# usblink.net
KiCad netlist of a schematic drawn in EAGLE
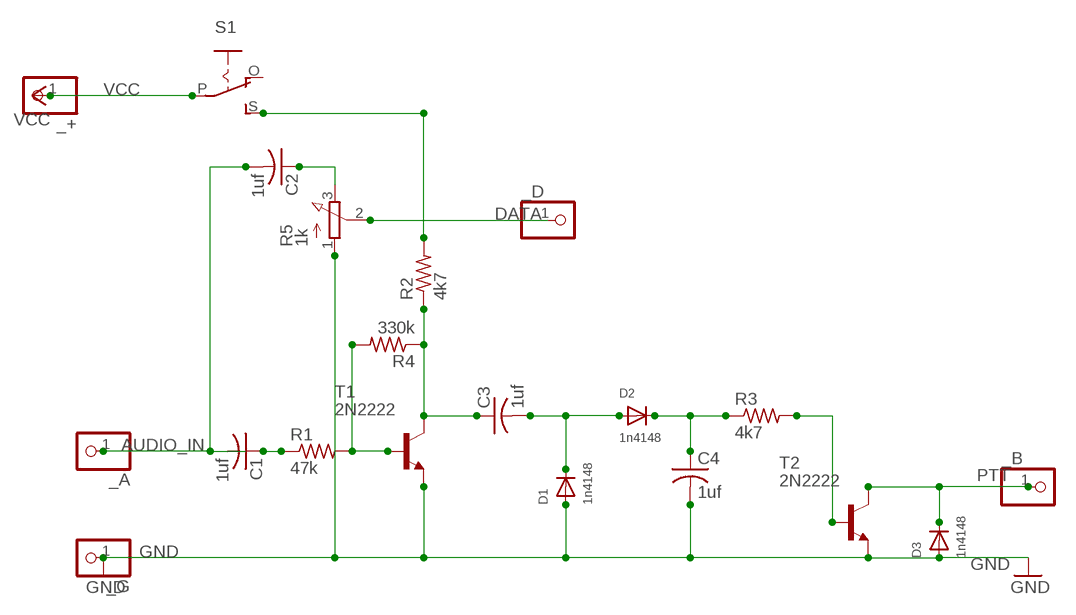
[diagram p0: schematic, sheet 1]

(export (version "E")
  (design (tool "Eeschema 10.0.6"))
  (components
    (comp (ref "C1")
      (value "1uf")
      (footprint "eagle-import:C025-030X050")
      (libsource (lib "eagle-import") (part "C-US025-030X050"))
    )
    (comp (ref "C2")
      (value "1uf")
      (footprint "eagle-import:C025-030X050")
      (libsource (lib "eagle-import") (part "C-US025-030X050"))
    )
    (comp (ref "C3")
      (value "1uf")
      (footprint "eagle-import:C025-030X050")
      (libsource (lib "eagle-import") (part "C-US025-030X050"))
    )
    (comp (ref "C4")
      (value "1uf")
      (footprint "eagle-import:C025-030X050")
      (libsource (lib "eagle-import") (part "C-US025-030X050"))
    )
    (comp (ref "D1")
      (value "1n4148")
      (footprint "eagle-import:DO-1N4148")
      (libsource (lib "eagle-import") (part "DIODEDO-1N4148"))
    )
    (comp (ref "D2")
      (value "1n4148")
      (footprint "eagle-import:DO-1N4148")
      (libsource (lib "eagle-import") (part "DIODEDO-1N4148"))
    )
    (comp (ref "D3")
      (value "1n4148")
      (footprint "eagle-import:DO-1N4148")
      (libsource (lib "eagle-import") (part "DIODEDO-1N4148"))
    )
    (comp (ref "R1")
      (value "47k")
      (footprint "eagle-import:0204_7")
      (libsource (lib "eagle-import") (part "R-US_0204/7"))
    )
    (comp (ref "R2")
      (value "4k7")
      (footprint "eagle-import:0204_7")
      (libsource (lib "eagle-import") (part "R-US_0204/7"))
    )
    (comp (ref "R3")
      (value "4k7")
      (footprint "eagle-import:0204_7")
      (libsource (lib "eagle-import") (part "R-US_0204/7"))
    )
    (comp (ref "R4")
      (value "330k")
      (footprint "eagle-import:0204_7")
      (libsource (lib "eagle-import") (part "R-US_0204/7"))
    )
    (comp (ref "R5")
      (value "1k")
      (footprint "eagle-import:3RP_1610N")
      (libsource (lib "eagle-import") (part "3RP/1610N"))
    )
    (comp (ref "S1")
      (value "EG1218S")
      (footprint "eagle-import:EG1218")
      (libsource (lib "eagle-import") (part "EG1218S"))
    )
    (comp (ref "T1")
      (value "2N2222")
      (footprint "eagle-import:TO92-EBC-OVAL")
      (libsource (lib "eagle-import") (part "2N2222"))
    )
    (comp (ref "T2")
      (value "2N2222")
      (footprint "eagle-import:TO92-EBC-OVAL")
      (libsource (lib "eagle-import") (part "2N2222"))
    )
    (comp (ref "_+")
      (value "PINHD-1X1CB")
      (footprint "eagle-import:1X01-CLEANBIG")
      (libsource (lib "eagle-import") (part "PINHD-1X1CB"))
    )
    (comp (ref "_A")
      (value "PINHD-1X1CB")
      (footprint "eagle-import:1X01-CLEANBIG")
      (libsource (lib "eagle-import") (part "PINHD-1X1CB"))
    )
    (comp (ref "_B")
      (value "PINHD-1X1CB")
      (footprint "eagle-import:1X01-CLEANBIG")
      (libsource (lib "eagle-import") (part "PINHD-1X1CB"))
    )
    (comp (ref "_D")
      (value "PINHD-1X1CB")
      (footprint "eagle-import:1X01-CLEANBIG")
      (libsource (lib "eagle-import") (part "PINHD-1X1CB"))
    )
    (comp (ref "_G")
      (value "PINHD-1X1CB")
      (footprint "eagle-import:1X01-CLEANBIG")
      (libsource (lib "eagle-import") (part "PINHD-1X1CB"))
    )
  )
  (nets
    (net (code "1") (name "/AUDIO_IN") (class "Default")
      (node (ref "C1") (pin "2") (pinfunction "2_2") (pintype "passive"))
      (node (ref "C2") (pin "2") (pinfunction "2_2") (pintype "passive"))
      (node (ref "_A") (pin "1") (pinfunction "1_1") (pintype "passive"))
    )
    (net (code "2") (name "/DATA") (class "Default")
      (node (ref "R5") (pin "2") (pinfunction "S_2") (pintype "passive"))
      (node (ref "_D") (pin "1") (pinfunction "1_1") (pintype "passive"))
    )
    (net (code "3") (name "/PTT") (class "Default")
      (node (ref "D3") (pin "C") (pinfunction "C_C") (pintype "passive"))
      (node (ref "T2") (pin "C") (pinfunction "C_C") (pintype "passive"))
      (node (ref "_B") (pin "1") (pinfunction "1_1") (pintype "passive"))
    )
    (net (code "4") (name "GND") (class "Default")
      (node (ref "C4") (pin "2") (pinfunction "2_2") (pintype "passive"))
      (node (ref "D1") (pin "A") (pinfunction "A_A") (pintype "passive"))
      (node (ref "D3") (pin "A") (pinfunction "A_A") (pintype "passive"))
      (node (ref "R5") (pin "1") (pinfunction "A_1") (pintype "passive"))
      (node (ref "T1") (pin "E") (pinfunction "E_E") (pintype "passive"))
      (node (ref "T2") (pin "E") (pinfunction "E_E") (pintype "passive"))
      (node (ref "_G") (pin "1") (pinfunction "1_1") (pintype "passive"))
    )
    (net (code "5") (name "Net-(C1-Pad1)") (class "Default")
      (node (ref "C1") (pin "1") (pinfunction "1_1") (pintype "passive"))
      (node (ref "R1") (pin "1") (pinfunction "1_1") (pintype "passive"))
    )
    (net (code "6") (name "Net-(C3-Pad1)") (class "Default")
      (node (ref "C3") (pin "1") (pinfunction "1_1") (pintype "passive"))
      (node (ref "R2") (pin "1") (pinfunction "1_1") (pintype "passive"))
      (node (ref "R4") (pin "1") (pinfunction "1_1") (pintype "passive"))
      (node (ref "T1") (pin "C") (pinfunction "C_C") (pintype "passive"))
    )
    (net (code "7") (name "Net-(C3-Pad2)") (class "Default")
      (node (ref "C3") (pin "2") (pinfunction "2_2") (pintype "passive"))
      (node (ref "D1") (pin "C") (pinfunction "C_C") (pintype "passive"))
      (node (ref "D2") (pin "A") (pinfunction "A_A") (pintype "passive"))
    )
    (net (code "8") (name "Net-(C4-Pad1)") (class "Default")
      (node (ref "C4") (pin "1") (pinfunction "1_1") (pintype "passive"))
      (node (ref "D2") (pin "C") (pinfunction "C_C") (pintype "passive"))
      (node (ref "R3") (pin "1") (pinfunction "1_1") (pintype "passive"))
    )
    (net (code "9") (name "Net-(R1-Pad2)") (class "Default")
      (node (ref "R1") (pin "2") (pinfunction "2_2") (pintype "passive"))
      (node (ref "R4") (pin "2") (pinfunction "2_2") (pintype "passive"))
      (node (ref "T1") (pin "B") (pinfunction "B_B") (pintype "passive"))
    )
    (net (code "10") (name "Net-(R2-Pad2)") (class "Default")
      (node (ref "R2") (pin "2") (pinfunction "2_2") (pintype "passive"))
      (node (ref "S1") (pin "S") (pinfunction "S_S") (pintype "passive"))
    )
    (net (code "11") (name "Net-(R3-Pad2)") (class "Default")
      (node (ref "R3") (pin "2") (pinfunction "2_2") (pintype "passive"))
      (node (ref "T2") (pin "B") (pinfunction "B_B") (pintype "passive"))
    )
    (net (code "12") (name "Net-(R5-E)") (class "Default")
      (node (ref "C2") (pin "1") (pinfunction "1_1") (pintype "passive"))
      (node (ref "R5") (pin "3") (pinfunction "E_3") (pintype "passive"))
    )
    (net (code "13") (name "VCC") (class "Default")
      (node (ref "S1") (pin "P") (pinfunction "P_P") (pintype "passive"))
      (node (ref "_+") (pin "1") (pinfunction "1_1") (pintype "passive"))
    )
    (net (code "14") (name "unconnected-(S1-PadO)") (class "Default")
      (node (ref "S1") (pin "O") (pinfunction "O_O") (pintype "passive"))
    )
  )
)
